# BBB-SPI-FF-Cape.net
KiCad netlist of a schematic drawn in EAGLE
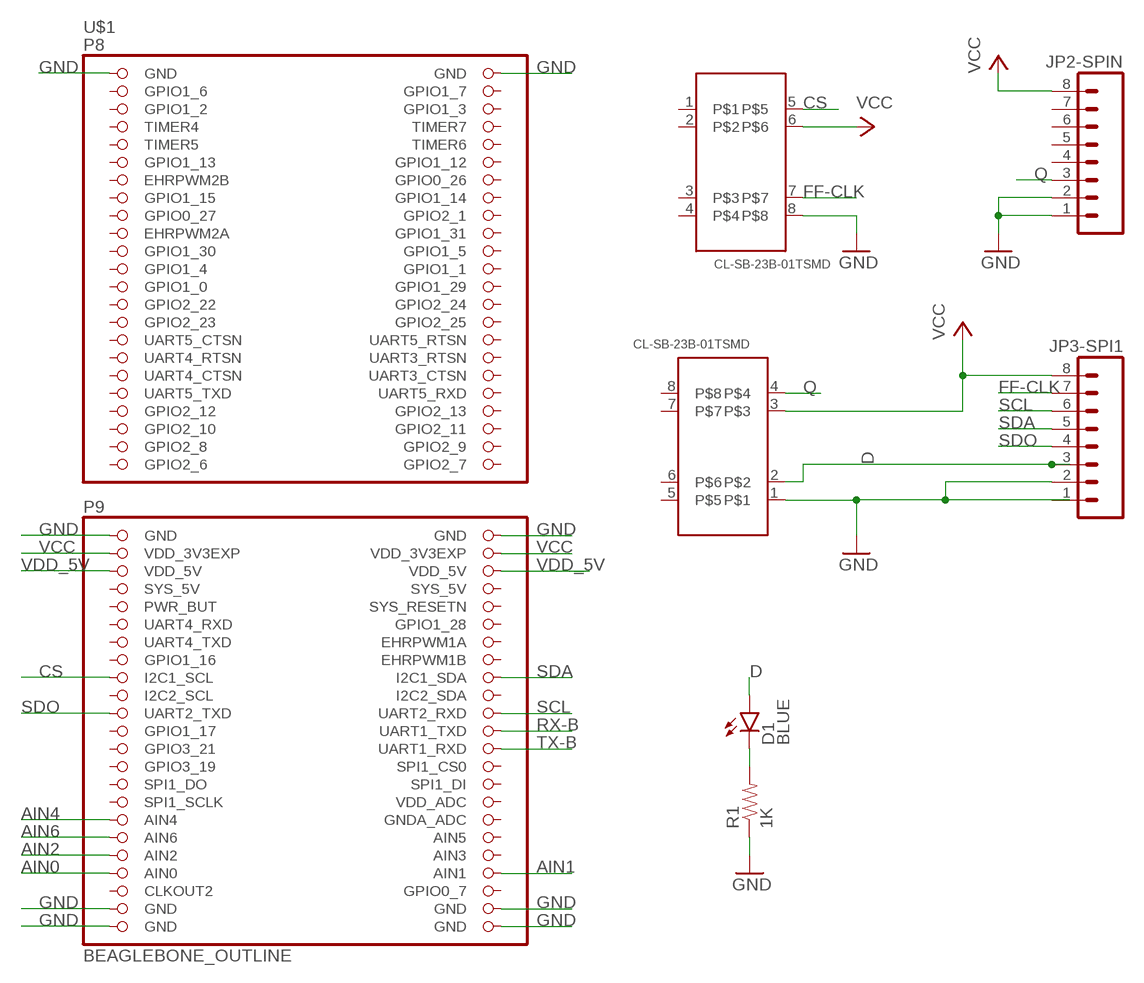
[diagram p0: schematic, sheet 1]

(export (version "E")
  (design (tool "Eeschema 10.0.6"))
  (components
    (comp (ref "D1")
      (value "BLUE")
      (footprint "eagle-import:LED-1206")
      (libsource (lib "eagle-import") (part "LED-BLUE1206"))
    )
    (comp (ref "JP2-SPIN")
      (value "M08BM08B-SRSS-TB")
      (footprint "eagle-import:BM08B-SRSS-TB")
      (libsource (lib "eagle-import") (part "M08BM08B-SRSS-TB"))
    )
    (comp (ref "JP3-SPI1")
      (value "M08BM08B-SRSS-TB")
      (footprint "eagle-import:BM08B-SRSS-TB")
      (libsource (lib "eagle-import") (part "M08BM08B-SRSS-TB"))
    )
    (comp (ref "R1")
      (value "1K")
      (footprint "eagle-import:1206")
      (libsource (lib "eagle-import") (part "RESISTOR1206"))
    )
    (comp (ref "U$1")
      (value "BEAGLEBONE_OUTLINE")
      (footprint "eagle-import:BEAGLEBONE_SHIELD")
      (libsource (lib "eagle-import") (part "BEAGLEBONE_OUTLINE"))
    )
    (comp (ref "U$2")
      (value "CL-SB-23B-01TSMD")
      (footprint "eagle-import:CL-SB-23B")
      (libsource (lib "eagle-import") (part "CL-SB-23B-01TSMD"))
    )
    (comp (ref "U$3")
      (value "CL-SB-23B-01TSMD")
      (footprint "eagle-import:CL-SB-23B")
      (libsource (lib "eagle-import") (part "CL-SB-23B-01TSMD"))
    )
  )
  (nets
    (net (code "1") (name "/AIN0") (class "Default")
      (node (ref "U$1") (pin "85") (pinfunction "AIN0_85") (pintype "power_in"))
    )
    (net (code "2") (name "/AIN1") (class "Default")
      (node (ref "U$1") (pin "86") (pinfunction "AIN1_86") (pintype "passive"))
    )
    (net (code "3") (name "/AIN2") (class "Default")
      (node (ref "U$1") (pin "83") (pinfunction "AIN2_83") (pintype "passive"))
    )
    (net (code "4") (name "/AIN4") (class "Default")
      (node (ref "U$1") (pin "79") (pinfunction "AIN4_79") (pintype "passive"))
    )
    (net (code "5") (name "/AIN6") (class "Default")
      (node (ref "U$1") (pin "81") (pinfunction "AIN6_81") (pintype "passive"))
    )
    (net (code "6") (name "/CS") (class "Default")
      (node (ref "U$1") (pin "63") (pinfunction "I2C1_SCL_63") (pintype "passive"))
      (node (ref "U$2") (pin "5") (pinfunction "P$5_5") (pintype "bidirectional"))
    )
    (net (code "7") (name "/D") (class "Default")
      (node (ref "D1") (pin "A") (pinfunction "A_A") (pintype "passive"))
      (node (ref "JP3-SPI1") (pin "3") (pinfunction "3_3") (pintype "passive"))
      (node (ref "U$3") (pin "2") (pinfunction "P$2_2") (pintype "bidirectional"))
    )
    (net (code "8") (name "/FF-CLK") (class "Default")
      (node (ref "JP3-SPI1") (pin "7") (pinfunction "7_7") (pintype "passive"))
      (node (ref "U$2") (pin "7") (pinfunction "P$7_7") (pintype "bidirectional"))
    )
    (net (code "9") (name "/Q") (class "Default")
      (node (ref "JP2-SPIN") (pin "3") (pinfunction "3_3") (pintype "passive"))
      (node (ref "U$3") (pin "4") (pinfunction "P$4_4") (pintype "bidirectional"))
    )
    (net (code "10") (name "/RX-B") (class "Default")
      (node (ref "U$1") (pin "70") (pinfunction "UART1_TXD_70") (pintype "passive"))
    )
    (net (code "11") (name "/SCL") (class "Default")
      (node (ref "JP3-SPI1") (pin "6") (pinfunction "6_6") (pintype "passive"))
      (node (ref "U$1") (pin "68") (pinfunction "UART2_RXD_68") (pintype "passive"))
    )
    (net (code "12") (name "/SDA") (class "Default")
      (node (ref "JP3-SPI1") (pin "5") (pinfunction "5_5") (pintype "passive"))
      (node (ref "U$1") (pin "64") (pinfunction "I2C1_SDA_64") (pintype "passive"))
    )
    (net (code "13") (name "/SDO") (class "Default")
      (node (ref "JP3-SPI1") (pin "4") (pinfunction "4_4") (pintype "passive"))
      (node (ref "U$1") (pin "67") (pinfunction "UART2_TXD_67") (pintype "passive"))
    )
    (net (code "14") (name "/SYS_5V") (class "Default")
      (node (ref "U$1") (pin "53") (pinfunction "SYS_5V_53") (pintype "power_in"))
    )
    (net (code "15") (name "/TX-B") (class "Default")
      (node (ref "U$1") (pin "72") (pinfunction "UART1_RXD_72") (pintype "passive"))
    )
    (net (code "16") (name "/VDD_5V") (class "Default")
      (node (ref "U$1") (pin "51") (pinfunction "VDD_5V_51") (pintype "power_in"))
      (node (ref "U$1") (pin "52") (pinfunction "VDD_5V_52") (pintype "power_in"))
    )
    (net (code "17") (name "GND") (class "Default")
      (node (ref "JP2-SPIN") (pin "1") (pinfunction "1_1") (pintype "passive"))
      (node (ref "JP2-SPIN") (pin "2") (pinfunction "2_2") (pintype "passive"))
      (node (ref "JP3-SPI1") (pin "2") (pinfunction "2_2") (pintype "passive"))
      (node (ref "R1") (pin "1") (pinfunction "1_1") (pintype "passive"))
      (node (ref "U$1") (pin "1") (pinfunction "GND_1") (pintype "power_in"))
      (node (ref "U$1") (pin "2") (pinfunction "GND_2") (pintype "power_in"))
      (node (ref "U$1") (pin "47") (pinfunction "GND_47") (pintype "power_in"))
      (node (ref "U$1") (pin "48") (pinfunction "GND_48") (pintype "power_in"))
      (node (ref "U$1") (pin "89") (pinfunction "GND_89") (pintype "power_in"))
      (node (ref "U$1") (pin "90") (pinfunction "GND_90") (pintype "power_in"))
      (node (ref "U$1") (pin "91") (pinfunction "GND_91") (pintype "power_in"))
      (node (ref "U$1") (pin "92") (pinfunction "GND_92") (pintype "power_in"))
      (node (ref "U$2") (pin "8") (pinfunction "P$8_8") (pintype "bidirectional"))
      (node (ref "U$3") (pin "1") (pinfunction "P$1_1") (pintype "bidirectional"))
    )
    (net (code "18") (name "Net-(D1-PadC)") (class "Default")
      (node (ref "D1") (pin "C") (pinfunction "C_C") (pintype "passive"))
      (node (ref "R1") (pin "2") (pinfunction "2_2") (pintype "passive"))
    )
    (net (code "19") (name "VCC") (class "Default")
      (node (ref "JP2-SPIN") (pin "8") (pinfunction "8_8") (pintype "passive"))
      (node (ref "JP3-SPI1") (pin "8") (pinfunction "8_8") (pintype "passive"))
      (node (ref "U$1") (pin "49") (pinfunction "VDD_3V3EXP_49") (pintype "power_in"))
      (node (ref "U$1") (pin "50") (pinfunction "VDD_3V3EXP_50") (pintype "power_in"))
      (node (ref "U$2") (pin "6") (pinfunction "P$6_6") (pintype "bidirectional"))
      (node (ref "U$3") (pin "3") (pinfunction "P$3_3") (pintype "bidirectional"))
    )
    (net (code "20") (name "unconnected-(JP2-SPIN-Pad4)") (class "Default")
      (node (ref "JP2-SPIN") (pin "4") (pinfunction "4_4") (pintype "passive"))
    )
    (net (code "21") (name "unconnected-(JP2-SPIN-Pad5)") (class "Default")
      (node (ref "JP2-SPIN") (pin "5") (pinfunction "5_5") (pintype "passive"))
    )
    (net (code "22") (name "unconnected-(JP2-SPIN-Pad6)") (class "Default")
      (node (ref "JP2-SPIN") (pin "6") (pinfunction "6_6") (pintype "passive"))
    )
    (net (code "23") (name "unconnected-(JP2-SPIN-Pad7)") (class "Default")
      (node (ref "JP2-SPIN") (pin "7") (pinfunction "7_7") (pintype "passive"))
    )
    (net (code "24") (name "unconnected-(JP3-SPI1-Pad1)") (class "Default")
      (node (ref "JP3-SPI1") (pin "1") (pinfunction "1_1") (pintype "passive"))
    )
    (net (code "25") (name "unconnected-(U$1-AIN3-Pad84)") (class "Default")
      (node (ref "U$1") (pin "84") (pinfunction "AIN3_84") (pintype "passive"))
    )
    (net (code "26") (name "unconnected-(U$1-AIN5-Pad82)") (class "Default")
      (node (ref "U$1") (pin "82") (pinfunction "AIN5_82") (pintype "passive"))
    )
    (net (code "27") (name "unconnected-(U$1-CLKOUT2-Pad87)") (class "Default")
      (node (ref "U$1") (pin "87") (pinfunction "CLKOUT2_87") (pintype "input"))
    )
    (net (code "28") (name "unconnected-(U$1-EHRPWM1A-Pad60)") (class "Default")
      (node (ref "U$1") (pin "60") (pinfunction "EHRPWM1A_60") (pintype "passive"))
    )
    (net (code "29") (name "unconnected-(U$1-EHRPWM1B-Pad62)") (class "Default")
      (node (ref "U$1") (pin "62") (pinfunction "EHRPWM1B_62") (pintype "passive"))
    )
    (net (code "30") (name "unconnected-(U$1-EHRPWM2A-Pad19)") (class "Default")
      (node (ref "U$1") (pin "19") (pinfunction "EHRPWM2A_19") (pintype "passive"))
    )
    (net (code "31") (name "unconnected-(U$1-EHRPWM2B-Pad13)") (class "Default")
      (node (ref "U$1") (pin "13") (pinfunction "EHRPWM2B_13") (pintype "passive"))
    )
    (net (code "32") (name "unconnected-(U$1-GNDA_ADC-Pad80)") (class "Default")
      (node (ref "U$1") (pin "80") (pinfunction "GNDA_ADC_80") (pintype "passive"))
    )
    (net (code "33") (name "unconnected-(U$1-GPIO0_7-Pad88)") (class "Default")
      (node (ref "U$1") (pin "88") (pinfunction "GPIO0_7_88") (pintype "passive"))
    )
    (net (code "34") (name "unconnected-(U$1-GPIO0_26-Pad14)") (class "Default")
      (node (ref "U$1") (pin "14") (pinfunction "GPIO0_26_14") (pintype "passive"))
    )
    (net (code "35") (name "unconnected-(U$1-GPIO0_27-Pad17)") (class "Default")
      (node (ref "U$1") (pin "17") (pinfunction "GPIO0_27_17") (pintype "passive"))
    )
    (net (code "36") (name "unconnected-(U$1-GPIO1_0-Pad25)") (class "Default")
      (node (ref "U$1") (pin "25") (pinfunction "GPIO1_0_25") (pintype "passive"))
    )
    (net (code "37") (name "unconnected-(U$1-GPIO1_1-Pad24)") (class "Default")
      (node (ref "U$1") (pin "24") (pinfunction "GPIO1_1_24") (pintype "passive"))
    )
    (net (code "38") (name "unconnected-(U$1-GPIO1_2-Pad5)") (class "Default")
      (node (ref "U$1") (pin "5") (pinfunction "GPIO1_2_5") (pintype "passive"))
    )
    (net (code "39") (name "unconnected-(U$1-GPIO1_3-Pad6)") (class "Default")
      (node (ref "U$1") (pin "6") (pinfunction "GPIO1_3_6") (pintype "passive"))
    )
    (net (code "40") (name "unconnected-(U$1-GPIO1_4-Pad23)") (class "Default")
      (node (ref "U$1") (pin "23") (pinfunction "GPIO1_4_23") (pintype "passive"))
    )
    (net (code "41") (name "unconnected-(U$1-GPIO1_5-Pad22)") (class "Default")
      (node (ref "U$1") (pin "22") (pinfunction "GPIO1_5_22") (pintype "passive"))
    )
    (net (code "42") (name "unconnected-(U$1-GPIO1_6-Pad3)") (class "Default")
      (node (ref "U$1") (pin "3") (pinfunction "GPIO1_6_3") (pintype "passive"))
    )
    (net (code "43") (name "unconnected-(U$1-GPIO1_7-Pad4)") (class "Default")
      (node (ref "U$1") (pin "4") (pinfunction "GPIO1_7_4") (pintype "passive"))
    )
    (net (code "44") (name "unconnected-(U$1-GPIO1_12-Pad12)") (class "Default")
      (node (ref "U$1") (pin "12") (pinfunction "GPIO1_12_12") (pintype "passive"))
    )
    (net (code "45") (name "unconnected-(U$1-GPIO1_13-Pad11)") (class "Default")
      (node (ref "U$1") (pin "11") (pinfunction "GPIO1_13_11") (pintype "passive"))
    )
    (net (code "46") (name "unconnected-(U$1-GPIO1_14-Pad16)") (class "Default")
      (node (ref "U$1") (pin "16") (pinfunction "GPIO1_14_16") (pintype "passive"))
    )
    (net (code "47") (name "unconnected-(U$1-GPIO1_15-Pad15)") (class "Default")
      (node (ref "U$1") (pin "15") (pinfunction "GPIO1_15_15") (pintype "passive"))
    )
    (net (code "48") (name "unconnected-(U$1-GPIO1_16-Pad61)") (class "Default")
      (node (ref "U$1") (pin "61") (pinfunction "GPIO1_16_61") (pintype "passive"))
    )
    (net (code "49") (name "unconnected-(U$1-GPIO1_17-Pad69)") (class "Default")
      (node (ref "U$1") (pin "69") (pinfunction "GPIO1_17_69") (pintype "passive"))
    )
    (net (code "50") (name "unconnected-(U$1-GPIO1_28-Pad58)") (class "Default")
      (node (ref "U$1") (pin "58") (pinfunction "GPIO1_28_58") (pintype "passive"))
    )
    (net (code "51") (name "unconnected-(U$1-GPIO1_29-Pad26)") (class "Default")
      (node (ref "U$1") (pin "26") (pinfunction "GPIO1_29_26") (pintype "passive"))
    )
    (net (code "52") (name "unconnected-(U$1-GPIO1_30-Pad21)") (class "Default")
      (node (ref "U$1") (pin "21") (pinfunction "GPIO1_30_21") (pintype "passive"))
    )
    (net (code "53") (name "unconnected-(U$1-GPIO1_31-Pad20)") (class "Default")
      (node (ref "U$1") (pin "20") (pinfunction "GPIO1_31_20") (pintype "passive"))
    )
    (net (code "54") (name "unconnected-(U$1-GPIO2_1-Pad18)") (class "Default")
      (node (ref "U$1") (pin "18") (pinfunction "GPIO2_1_18") (pintype "passive"))
    )
    (net (code "55") (name "unconnected-(U$1-GPIO2_6-Pad45)") (class "Default")
      (node (ref "U$1") (pin "45") (pinfunction "GPIO2_6_45") (pintype "passive"))
    )
    (net (code "56") (name "unconnected-(U$1-GPIO2_7-Pad46)") (class "Default")
      (node (ref "U$1") (pin "46") (pinfunction "GPIO2_7_46") (pintype "passive"))
    )
    (net (code "57") (name "unconnected-(U$1-GPIO2_8-Pad43)") (class "Default")
      (node (ref "U$1") (pin "43") (pinfunction "GPIO2_8_43") (pintype "passive"))
    )
    (net (code "58") (name "unconnected-(U$1-GPIO2_9-Pad44)") (class "Default")
      (node (ref "U$1") (pin "44") (pinfunction "GPIO2_9_44") (pintype "passive"))
    )
    (net (code "59") (name "unconnected-(U$1-GPIO2_10-Pad41)") (class "Default")
      (node (ref "U$1") (pin "41") (pinfunction "GPIO2_10_41") (pintype "passive"))
    )
    (net (code "60") (name "unconnected-(U$1-GPIO2_11-Pad42)") (class "Default")
      (node (ref "U$1") (pin "42") (pinfunction "GPIO2_11_42") (pintype "passive"))
    )
    (net (code "61") (name "unconnected-(U$1-GPIO2_12-Pad39)") (class "Default")
      (node (ref "U$1") (pin "39") (pinfunction "GPIO2_12_39") (pintype "passive"))
    )
    (net (code "62") (name "unconnected-(U$1-GPIO2_13-Pad40)") (class "Default")
      (node (ref "U$1") (pin "40") (pinfunction "GPIO2_13_40") (pintype "passive"))
    )
    (net (code "63") (name "unconnected-(U$1-GPIO2_22-Pad27)") (class "Default")
      (node (ref "U$1") (pin "27") (pinfunction "GPIO2_22_27") (pintype "passive"))
    )
    (net (code "64") (name "unconnected-(U$1-GPIO2_23-Pad29)") (class "Default")
      (node (ref "U$1") (pin "29") (pinfunction "GPIO2_23_29") (pintype "passive"))
    )
    (net (code "65") (name "unconnected-(U$1-GPIO2_24-Pad28)") (class "Default")
      (node (ref "U$1") (pin "28") (pinfunction "GPIO2_24_28") (pintype "passive"))
    )
    (net (code "66") (name "unconnected-(U$1-GPIO2_25-Pad30)") (class "Default")
      (node (ref "U$1") (pin "30") (pinfunction "GPIO2_25_30") (pintype "passive"))
    )
    (net (code "67") (name "unconnected-(U$1-GPIO3_19-Pad73)") (class "Default")
      (node (ref "U$1") (pin "73") (pinfunction "GPIO3_19_73") (pintype "passive"))
    )
    (net (code "68") (name "unconnected-(U$1-GPIO3_21-Pad71)") (class "Default")
      (node (ref "U$1") (pin "71") (pinfunction "GPIO3_21_71") (pintype "passive"))
    )
    (net (code "69") (name "unconnected-(U$1-I2C2_SCL-Pad65)") (class "Default")
      (node (ref "U$1") (pin "65") (pinfunction "I2C2_SCL_65") (pintype "passive"))
    )
    (net (code "70") (name "unconnected-(U$1-I2C2_SDA-Pad66)") (class "Default")
      (node (ref "U$1") (pin "66") (pinfunction "I2C2_SDA_66") (pintype "passive"))
    )
    (net (code "71") (name "unconnected-(U$1-PWR_BUT-Pad55)") (class "Default")
      (node (ref "U$1") (pin "55") (pinfunction "PWR_BUT_55") (pintype "passive"))
    )
    (net (code "72") (name "unconnected-(U$1-SPI1_CS0-Pad74)") (class "Default")
      (node (ref "U$1") (pin "74") (pinfunction "SPI1_CS0_74") (pintype "passive"))
    )
    (net (code "73") (name "unconnected-(U$1-SPI1_DI-Pad76)") (class "Default")
      (node (ref "U$1") (pin "76") (pinfunction "SPI1_DI_76") (pintype "passive"))
    )
    (net (code "74") (name "unconnected-(U$1-SPI1_DO-Pad75)") (class "Default")
      (node (ref "U$1") (pin "75") (pinfunction "SPI1_DO_75") (pintype "passive"))
    )
    (net (code "75") (name "unconnected-(U$1-SPI1_SCLK-Pad77)") (class "Default")
      (node (ref "U$1") (pin "77") (pinfunction "SPI1_SCLK_77") (pintype "passive"))
    )
    (net (code "76") (name "unconnected-(U$1-SYS_5V-Pad54)") (class "Default")
      (node (ref "U$1") (pin "54") (pinfunction "SYS_5V_54") (pintype "passive"))
    )
    (net (code "77") (name "unconnected-(U$1-SYS_RESETN-Pad56)") (class "Default")
      (node (ref "U$1") (pin "56") (pinfunction "SYS_RESETN_56") (pintype "passive"))
    )
    (net (code "78") (name "unconnected-(U$1-TIMER4-Pad7)") (class "Default")
      (node (ref "U$1") (pin "7") (pinfunction "TIMER4_7") (pintype "passive"))
    )
    (net (code "79") (name "unconnected-(U$1-TIMER5-Pad9)") (class "Default")
      (node (ref "U$1") (pin "9") (pinfunction "TIMER5_9") (pintype "passive"))
    )
    (net (code "80") (name "unconnected-(U$1-TIMER6-Pad10)") (class "Default")
      (node (ref "U$1") (pin "10") (pinfunction "TIMER6_10") (pintype "passive"))
    )
    (net (code "81") (name "unconnected-(U$1-TIMER7-Pad8)") (class "Default")
      (node (ref "U$1") (pin "8") (pinfunction "TIMER7_8") (pintype "passive"))
    )
    (net (code "82") (name "unconnected-(U$1-UART3_CTSN-Pad36)") (class "Default")
      (node (ref "U$1") (pin "36") (pinfunction "UART3_CTSN_36") (pintype "passive"))
    )
    (net (code "83") (name "unconnected-(U$1-UART3_RTSN-Pad34)") (class "Default")
      (node (ref "U$1") (pin "34") (pinfunction "UART3_RTSN_34") (pintype "passive"))
    )
    (net (code "84") (name "unconnected-(U$1-UART4_CTSN-Pad35)") (class "Default")
      (node (ref "U$1") (pin "35") (pinfunction "UART4_CTSN_35") (pintype "passive"))
    )
    (net (code "85") (name "unconnected-(U$1-UART4_RTSN-Pad33)") (class "Default")
      (node (ref "U$1") (pin "33") (pinfunction "UART4_RTSN_33") (pintype "passive"))
    )
    (net (code "86") (name "unconnected-(U$1-UART4_RXD-Pad57)") (class "Default")
      (node (ref "U$1") (pin "57") (pinfunction "UART4_RXD_57") (pintype "passive"))
    )
    (net (code "87") (name "unconnected-(U$1-UART4_TXD-Pad59)") (class "Default")
      (node (ref "U$1") (pin "59") (pinfunction "UART4_TXD_59") (pintype "passive"))
    )
    (net (code "88") (name "unconnected-(U$1-UART5_CTSN-Pad31)") (class "Default")
      (node (ref "U$1") (pin "31") (pinfunction "UART5_CTSN_31") (pintype "passive"))
    )
    (net (code "89") (name "unconnected-(U$1-UART5_RTSN-Pad32)") (class "Default")
      (node (ref "U$1") (pin "32") (pinfunction "UART5_RTSN_32") (pintype "passive"))
    )
    (net (code "90") (name "unconnected-(U$1-UART5_RXD-Pad38)") (class "Default")
      (node (ref "U$1") (pin "38") (pinfunction "UART5_RXD_38") (pintype "passive"))
    )
    (net (code "91") (name "unconnected-(U$1-UART5_TXD-Pad37)") (class "Default")
      (node (ref "U$1") (pin "37") (pinfunction "UART5_TXD_37") (pintype "passive"))
    )
    (net (code "92") (name "unconnected-(U$1-VDD_ADC-Pad78)") (class "Default")
      (node (ref "U$1") (pin "78") (pinfunction "VDD_ADC_78") (pintype "passive"))
    )
    (net (code "93") (name "unconnected-(U$2-P$1-Pad1)") (class "Default")
      (node (ref "U$2") (pin "1") (pinfunction "P$1_1") (pintype "bidirectional"))
    )
    (net (code "94") (name "unconnected-(U$2-P$2-Pad2)") (class "Default")
      (node (ref "U$2") (pin "2") (pinfunction "P$2_2") (pintype "bidirectional"))
    )
    (net (code "95") (name "unconnected-(U$2-P$3-Pad3)") (class "Default")
      (node (ref "U$2") (pin "3") (pinfunction "P$3_3") (pintype "bidirectional"))
    )
    (net (code "96") (name "unconnected-(U$2-P$4-Pad4)") (class "Default")
      (node (ref "U$2") (pin "4") (pinfunction "P$4_4") (pintype "bidirectional"))
    )
    (net (code "97") (name "unconnected-(U$3-P$5-Pad5)") (class "Default")
      (node (ref "U$3") (pin "5") (pinfunction "P$5_5") (pintype "bidirectional"))
    )
    (net (code "98") (name "unconnected-(U$3-P$6-Pad6)") (class "Default")
      (node (ref "U$3") (pin "6") (pinfunction "P$6_6") (pintype "bidirectional"))
    )
    (net (code "99") (name "unconnected-(U$3-P$7-Pad7)") (class "Default")
      (node (ref "U$3") (pin "7") (pinfunction "P$7_7") (pintype "bidirectional"))
    )
    (net (code "100") (name "unconnected-(U$3-P$8-Pad8)") (class "Default")
      (node (ref "U$3") (pin "8") (pinfunction "P$8_8") (pintype "bidirectional"))
    )
  )
)
